# TP_IHM_CONNECTOR.net
KiCad netlist of a schematic drawn in Altium Designer
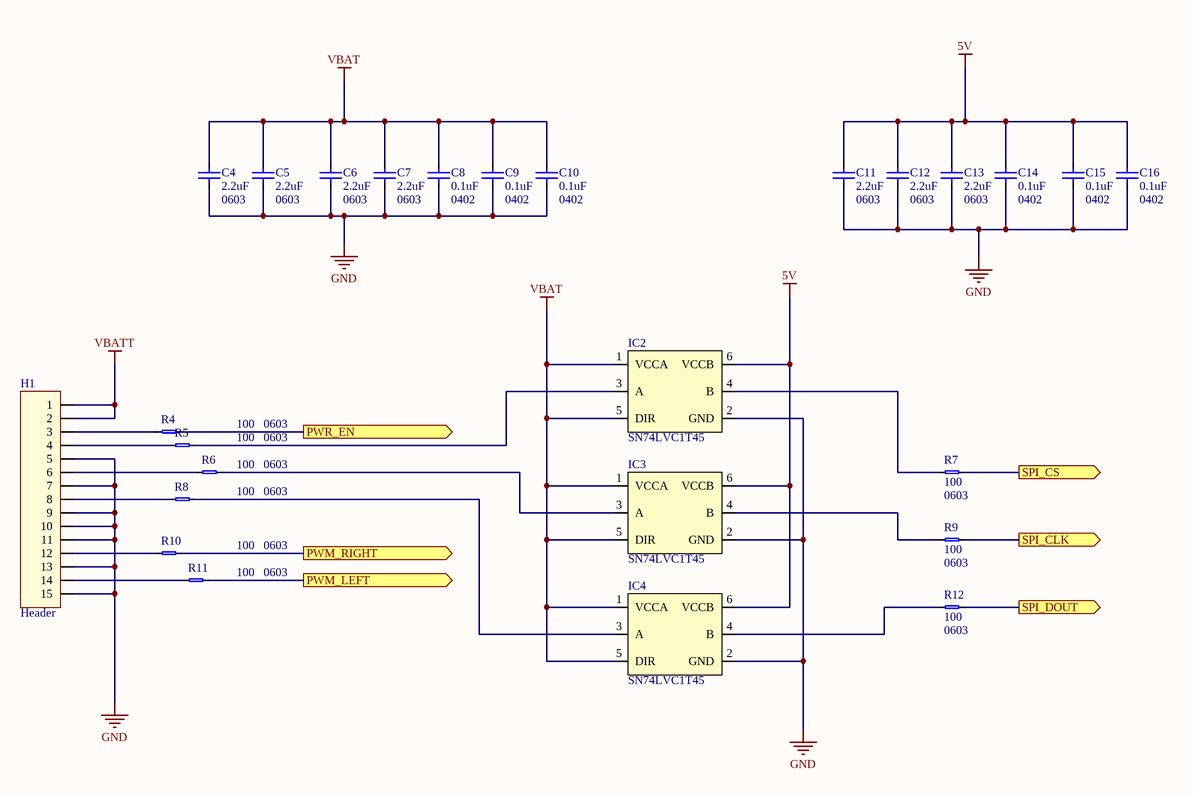
[diagram p0: TP_IHM_CONNECTOR.SchDoc]

(export (version "E")
  (design (tool "Eeschema 10.0.6"))
  (components
    (comp (ref "C4")
      (value "2.2uF")
      (footprint "0603_CAP_LD")
      (description "Ceramic Capacitor")
      (fields (field (name "PACKAGE") "0603") (field (name "Comment") "CerCap"))
      (libsource (lib "TpGiven") (part "CerCap"))
    )
    (comp (ref "C5")
      (value "2.2uF")
      (footprint "0603_CAP_LD")
      (description "Ceramic Capacitor")
      (fields (field (name "PACKAGE") "0603") (field (name "Comment") "CerCap"))
      (libsource (lib "TpGiven") (part "CerCap"))
    )
    (comp (ref "C6")
      (value "2.2uF")
      (footprint "0603_CAP_LD")
      (description "Ceramic Capacitor")
      (fields (field (name "PACKAGE") "0603") (field (name "Comment") "CerCap"))
      (libsource (lib "TpGiven") (part "CerCap"))
    )
    (comp (ref "C7")
      (value "2.2uF")
      (footprint "0603_CAP_LD")
      (description "Ceramic Capacitor")
      (fields (field (name "PACKAGE") "0603") (field (name "Comment") "CerCap"))
      (libsource (lib "TpGiven") (part "CerCap"))
    )
    (comp (ref "C8")
      (value "0.1uF")
      (footprint "0603_CAP_LD")
      (description "Ceramic Capacitor")
      (fields (field (name "PACKAGE") "0402") (field (name "Comment") "CerCap"))
      (libsource (lib "TpGiven") (part "CerCap"))
    )
    (comp (ref "C9")
      (value "0.1uF")
      (footprint "0603_CAP_LD")
      (description "Ceramic Capacitor")
      (fields (field (name "PACKAGE") "0402") (field (name "Comment") "CerCap"))
      (libsource (lib "TpGiven") (part "CerCap"))
    )
    (comp (ref "C10")
      (value "0.1uF")
      (footprint "0603_CAP_LD")
      (description "Ceramic Capacitor")
      (fields (field (name "PACKAGE") "0402") (field (name "Comment") "CerCap"))
      (libsource (lib "TpGiven") (part "CerCap"))
    )
    (comp (ref "C11")
      (value "2.2uF")
      (footprint "0603_CAP_LD")
      (description "Ceramic Capacitor")
      (fields (field (name "PACKAGE") "0603") (field (name "Comment") "CerCap"))
      (libsource (lib "TpGiven") (part "CerCap"))
    )
    (comp (ref "C12")
      (value "2.2uF")
      (footprint "0603_CAP_LD")
      (description "Ceramic Capacitor")
      (fields (field (name "PACKAGE") "0603") (field (name "Comment") "CerCap"))
      (libsource (lib "TpGiven") (part "CerCap"))
    )
    (comp (ref "C13")
      (value "2.2uF")
      (footprint "0603_CAP_LD")
      (description "Ceramic Capacitor")
      (fields (field (name "PACKAGE") "0603") (field (name "Comment") "CerCap"))
      (libsource (lib "TpGiven") (part "CerCap"))
    )
    (comp (ref "C14")
      (value "0.1uF")
      (footprint "0603_CAP_LD")
      (description "Ceramic Capacitor")
      (fields (field (name "PACKAGE") "0402") (field (name "Comment") "CerCap"))
      (libsource (lib "TpGiven") (part "CerCap"))
    )
    (comp (ref "C15")
      (value "0.1uF")
      (footprint "0603_CAP_LD")
      (description "Ceramic Capacitor")
      (fields (field (name "PACKAGE") "0402") (field (name "Comment") "CerCap"))
      (libsource (lib "TpGiven") (part "CerCap"))
    )
    (comp (ref "C16")
      (value "0.1uF")
      (footprint "0603_CAP_LD")
      (description "Ceramic Capacitor")
      (fields (field (name "PACKAGE") "0402") (field (name "Comment") "CerCap"))
      (libsource (lib "TpGiven") (part "CerCap"))
    )
    (comp (ref "H1")
      (value "Header")
      (footprint "653115131822")
      (description "Header 15x1")
      (libsource (lib "TpGiven") (part "HEADER_15x1"))
    )
    (comp (ref "IC2")
      (value "SN74LVC1T45")
      (footprint "MO-203AB_LD")
      (description "Single Bit Dual Supply Buffer")
      (libsource (lib "TpGiven") (part "SN74LVC1T45"))
    )
    (comp (ref "IC3")
      (value "SN74LVC1T45")
      (footprint "MO-203AB_LD")
      (description "Single Bit Dual Supply Buffer")
      (libsource (lib "TpGiven") (part "SN74LVC1T45"))
    )
    (comp (ref "IC4")
      (value "SN74LVC1T45")
      (footprint "MO-203AB_LD")
      (description "Single Bit Dual Supply Buffer")
      (libsource (lib "TpGiven") (part "SN74LVC1T45"))
    )
    (comp (ref "R4")
      (value "Resistor")
      (footprint "0603_RES_LD")
      (fields (field (name "PRECISION") "100") (field (name "PACKAGE") "0603"))
      (libsource (lib "TpGiven") (part "Resistor"))
    )
    (comp (ref "R5")
      (value "Resistor")
      (footprint "0603_RES_LD")
      (fields (field (name "PRECISION") "100") (field (name "PACKAGE") "0603"))
      (libsource (lib "TpGiven") (part "Resistor"))
    )
    (comp (ref "R6")
      (value "Resistor")
      (footprint "0603_RES_LD")
      (fields (field (name "PRECISION") "100") (field (name "PACKAGE") "0603"))
      (libsource (lib "TpGiven") (part "Resistor"))
    )
    (comp (ref "R7")
      (value "100")
      (footprint "0603_RES_LD")
      (description "Resistor")
      (fields (field (name "PACKAGE") "0603"))
      (libsource (lib "TpGiven") (part "Resistor"))
    )
    (comp (ref "R8")
      (value "Resistor")
      (footprint "0603_RES_LD")
      (fields (field (name "PRECISION") "100") (field (name "PACKAGE") "0603"))
      (libsource (lib "TpGiven") (part "Resistor"))
    )
    (comp (ref "R9")
      (value "100")
      (footprint "0603_RES_LD")
      (description "Resistor")
      (fields (field (name "PACKAGE") "0603"))
      (libsource (lib "TpGiven") (part "Resistor"))
    )
    (comp (ref "R10")
      (value "Resistor")
      (footprint "0603_RES_LD")
      (fields (field (name "PRECISION") "100") (field (name "PACKAGE") "0603"))
      (libsource (lib "TpGiven") (part "Resistor"))
    )
    (comp (ref "R11")
      (value "Resistor")
      (footprint "0603_RES_LD")
      (fields (field (name "PRECISION") "100") (field (name "PACKAGE") "0603"))
      (libsource (lib "TpGiven") (part "Resistor"))
    )
    (comp (ref "R12")
      (value "100")
      (footprint "0603_RES_LD")
      (description "Resistor")
      (fields (field (name "PACKAGE") "0603"))
      (libsource (lib "TpGiven") (part "Resistor"))
    )
  )
  (nets
    (net (code "1") (name "/PWM_LEFT") (class "Default")
      (node (ref "R11") (pin "2") (pinfunction "2_2") (pintype "passive"))
    )
    (net (code "2") (name "/PWM_RIGHT") (class "Default")
      (node (ref "R10") (pin "2") (pinfunction "2_2") (pintype "passive"))
    )
    (net (code "3") (name "/PWR_EN") (class "Default")
      (node (ref "R4") (pin "2") (pinfunction "2_2") (pintype "passive"))
    )
    (net (code "4") (name "/SPI_CLK") (class "Default")
      (node (ref "R9") (pin "2") (pinfunction "2_2") (pintype "passive"))
    )
    (net (code "5") (name "/SPI_CS") (class "Default")
      (node (ref "R7") (pin "2") (pinfunction "2_2") (pintype "passive"))
    )
    (net (code "6") (name "/SPI_DOUT") (class "Default")
      (node (ref "R12") (pin "2") (pinfunction "2_2") (pintype "passive"))
    )
    (net (code "7") (name "5V") (class "Default")
      (node (ref "C11") (pin "2") (pinfunction "2_2") (pintype "passive"))
      (node (ref "C12") (pin "2") (pinfunction "2_2") (pintype "passive"))
      (node (ref "C13") (pin "2") (pinfunction "2_2") (pintype "passive"))
      (node (ref "C14") (pin "2") (pinfunction "2_2") (pintype "passive"))
      (node (ref "C15") (pin "2") (pinfunction "2_2") (pintype "passive"))
      (node (ref "C16") (pin "2") (pinfunction "2_2") (pintype "passive"))
      (node (ref "IC2") (pin "6") (pinfunction "VCCB_6") (pintype "passive"))
      (node (ref "IC3") (pin "6") (pinfunction "VCCB_6") (pintype "passive"))
      (node (ref "IC4") (pin "6") (pinfunction "VCCB_6") (pintype "passive"))
    )
    (net (code "8") (name "GND") (class "Default")
      (node (ref "C10") (pin "1") (pinfunction "1_1") (pintype "passive"))
      (node (ref "C11") (pin "1") (pinfunction "1_1") (pintype "passive"))
      (node (ref "C12") (pin "1") (pinfunction "1_1") (pintype "passive"))
      (node (ref "C13") (pin "1") (pinfunction "1_1") (pintype "passive"))
      (node (ref "C14") (pin "1") (pinfunction "1_1") (pintype "passive"))
      (node (ref "C15") (pin "1") (pinfunction "1_1") (pintype "passive"))
      (node (ref "C16") (pin "1") (pinfunction "1_1") (pintype "passive"))
      (node (ref "C4") (pin "1") (pinfunction "1_1") (pintype "passive"))
      (node (ref "C5") (pin "1") (pinfunction "1_1") (pintype "passive"))
      (node (ref "C6") (pin "1") (pinfunction "1_1") (pintype "passive"))
      (node (ref "C7") (pin "1") (pinfunction "1_1") (pintype "passive"))
      (node (ref "C8") (pin "1") (pinfunction "1_1") (pintype "passive"))
      (node (ref "C9") (pin "1") (pinfunction "1_1") (pintype "passive"))
      (node (ref "H1") (pin "10") (pinfunction "10_10") (pintype "passive"))
      (node (ref "H1") (pin "11") (pinfunction "11_11") (pintype "passive"))
      (node (ref "H1") (pin "13") (pinfunction "13_13") (pintype "passive"))
      (node (ref "H1") (pin "15") (pinfunction "15_15") (pintype "passive"))
      (node (ref "H1") (pin "5") (pinfunction "5_5") (pintype "passive"))
      (node (ref "H1") (pin "7") (pinfunction "7_7") (pintype "passive"))
      (node (ref "H1") (pin "9") (pinfunction "9_9") (pintype "passive"))
      (node (ref "IC2") (pin "2") (pinfunction "GND_2") (pintype "passive"))
      (node (ref "IC3") (pin "2") (pinfunction "GND_2") (pintype "passive"))
      (node (ref "IC4") (pin "2") (pinfunction "GND_2") (pintype "passive"))
    )
    (net (code "9") (name "Net-(H1-Pad3)") (class "Default")
      (node (ref "H1") (pin "3") (pinfunction "3_3") (pintype "passive"))
      (node (ref "R4") (pin "1") (pinfunction "1_1") (pintype "passive"))
    )
    (net (code "10") (name "Net-(H1-Pad4)") (class "Default")
      (node (ref "H1") (pin "4") (pinfunction "4_4") (pintype "passive"))
      (node (ref "R5") (pin "1") (pinfunction "1_1") (pintype "passive"))
    )
    (net (code "11") (name "Net-(H1-Pad6)") (class "Default")
      (node (ref "H1") (pin "6") (pinfunction "6_6") (pintype "passive"))
      (node (ref "R6") (pin "1") (pinfunction "1_1") (pintype "passive"))
    )
    (net (code "12") (name "Net-(H1-Pad8)") (class "Default")
      (node (ref "H1") (pin "8") (pinfunction "8_8") (pintype "passive"))
      (node (ref "R8") (pin "1") (pinfunction "1_1") (pintype "passive"))
    )
    (net (code "13") (name "Net-(H1-Pad12)") (class "Default")
      (node (ref "H1") (pin "12") (pinfunction "12_12") (pintype "passive"))
      (node (ref "R10") (pin "1") (pinfunction "1_1") (pintype "passive"))
    )
    (net (code "14") (name "Net-(H1-Pad14)") (class "Default")
      (node (ref "H1") (pin "14") (pinfunction "14_14") (pintype "passive"))
      (node (ref "R11") (pin "1") (pinfunction "1_1") (pintype "passive"))
    )
    (net (code "15") (name "Net-(IC2-A)") (class "Default")
      (node (ref "IC2") (pin "3") (pinfunction "A_3") (pintype "passive"))
      (node (ref "R5") (pin "2") (pinfunction "2_2") (pintype "passive"))
    )
    (net (code "16") (name "Net-(IC2-B)") (class "Default")
      (node (ref "IC2") (pin "4") (pinfunction "B_4") (pintype "passive"))
      (node (ref "R7") (pin "1") (pinfunction "1_1") (pintype "passive"))
    )
    (net (code "17") (name "Net-(IC3-A)") (class "Default")
      (node (ref "IC3") (pin "3") (pinfunction "A_3") (pintype "passive"))
      (node (ref "R6") (pin "2") (pinfunction "2_2") (pintype "passive"))
    )
    (net (code "18") (name "Net-(IC3-B)") (class "Default")
      (node (ref "IC3") (pin "4") (pinfunction "B_4") (pintype "passive"))
      (node (ref "R9") (pin "1") (pinfunction "1_1") (pintype "passive"))
    )
    (net (code "19") (name "Net-(IC4-A)") (class "Default")
      (node (ref "IC4") (pin "3") (pinfunction "A_3") (pintype "passive"))
      (node (ref "R8") (pin "2") (pinfunction "2_2") (pintype "passive"))
    )
    (net (code "20") (name "Net-(IC4-B)") (class "Default")
      (node (ref "IC4") (pin "4") (pinfunction "B_4") (pintype "passive"))
      (node (ref "R12") (pin "1") (pinfunction "1_1") (pintype "passive"))
    )
    (net (code "21") (name "VBAT") (class "Default")
      (node (ref "C10") (pin "2") (pinfunction "2_2") (pintype "passive"))
      (node (ref "C4") (pin "2") (pinfunction "2_2") (pintype "passive"))
      (node (ref "C5") (pin "2") (pinfunction "2_2") (pintype "passive"))
      (node (ref "C6") (pin "2") (pinfunction "2_2") (pintype "passive"))
      (node (ref "C7") (pin "2") (pinfunction "2_2") (pintype "passive"))
      (node (ref "C8") (pin "2") (pinfunction "2_2") (pintype "passive"))
      (node (ref "C9") (pin "2") (pinfunction "2_2") (pintype "passive"))
      (node (ref "IC2") (pin "1") (pinfunction "VCCA_1") (pintype "passive"))
      (node (ref "IC2") (pin "5") (pinfunction "DIR_5") (pintype "passive"))
      (node (ref "IC3") (pin "1") (pinfunction "VCCA_1") (pintype "passive"))
      (node (ref "IC3") (pin "5") (pinfunction "DIR_5") (pintype "passive"))
      (node (ref "IC4") (pin "1") (pinfunction "VCCA_1") (pintype "passive"))
      (node (ref "IC4") (pin "5") (pinfunction "DIR_5") (pintype "passive"))
    )
    (net (code "22") (name "VBATT") (class "Default")
      (node (ref "H1") (pin "1") (pinfunction "1_1") (pintype "passive"))
      (node (ref "H1") (pin "2") (pinfunction "2_2") (pintype "passive"))
    )
  )
)
